# CAN_ADM3053.net
KiCad netlist of a schematic drawn in Altium Designer
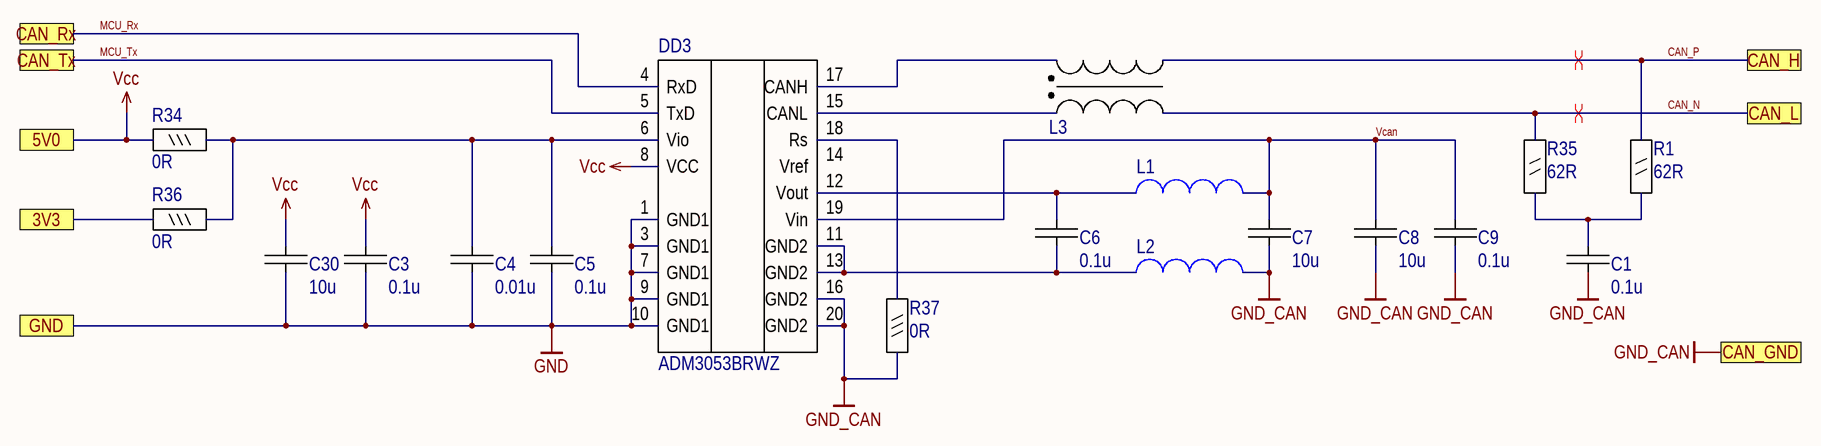
[diagram p0: CAN_ADM3053.SchDoc]

(export (version "E")
  (design (tool "Eeschema 10.0.6"))
  (components
    (comp (ref "C1")
      (value "0.1u")
      (footprint "C0603_IPC")
      (description "0.1uF ±10% 50V Ceramic Capacitor X7R 0603 (1608 Metric)")
      (fields (field (name "PARTNUMBER") "0.1u 50V") (field (name "MPN") "CL10B104KB8NNND"))
      (libsource (lib "DB_res_cap_ind") (part "C0603_GOST"))
    )
    (comp (ref "C3")
      (value "0.1u")
      (footprint "C0603_IPC")
      (description "0.1uF ±10% 50V Ceramic Capacitor X7R 0603 (1608 Metric)")
      (fields (field (name "PARTNUMBER") "0.1u 50V") (field (name "MPN") "CL10B104KB8NNND"))
      (libsource (lib "DB_res_cap_ind") (part "C0603_GOST"))
    )
    (comp (ref "C4")
      (value "0.01u")
      (footprint "C0603_IPC")
      (description "0.01uF ±10% 50V Ceramic Capacitor X7R 0603 (1608 Metric)")
      (fields (field (name "PARTNUMBER") "0.01u 50V") (field (name "MPN") "CC0603KRX7R9BB103"))
      (libsource (lib "DB_res_cap_ind") (part "C0603_GOST"))
    )
    (comp (ref "C5")
      (value "0.1u")
      (footprint "C0603_IPC")
      (description "0.1uF ±10% 50V Ceramic Capacitor X7R 0603 (1608 Metric)")
      (fields (field (name "PARTNUMBER") "0.1u 50V") (field (name "MPN") "CL10B104KB8NNND"))
      (libsource (lib "DB_res_cap_ind") (part "C0603_GOST"))
    )
    (comp (ref "C6")
      (value "0.1u")
      (footprint "C0603_IPC")
      (description "0.1uF ±10% 50V Ceramic Capacitor X7R 0603 (1608 Metric)")
      (fields (field (name "PARTNUMBER") "0.1u 50V") (field (name "MPN") "CL10B104KB8NNND"))
      (libsource (lib "DB_res_cap_ind") (part "C0603_GOST"))
    )
    (comp (ref "C7")
      (value "10u")
      (footprint "C0805_IPC")
      (description "10µF ±10% 10V Ceramic Capacitor X7R 0805 (2012 Metric)")
      (fields (field (name "PARTNUMBER") "10u 10V") (field (name "MPN") "CL21B106KPQNNNE"))
      (libsource (lib "DB_res_cap_ind") (part "C0603_GOST"))
    )
    (comp (ref "C8")
      (value "10u")
      (footprint "C0805_IPC")
      (description "10µF ±10% 10V Ceramic Capacitor X7R 0805 (2012 Metric)")
      (fields (field (name "PARTNUMBER") "10u 10V") (field (name "MPN") "CL21B106KPQNNNE"))
      (libsource (lib "DB_res_cap_ind") (part "C0603_GOST"))
    )
    (comp (ref "C9")
      (value "0.1u")
      (footprint "C0603_IPC")
      (description "0.1uF ±10% 50V Ceramic Capacitor X7R 0603 (1608 Metric)")
      (fields (field (name "PARTNUMBER") "0.1u 50V") (field (name "MPN") "CL10B104KB8NNND"))
      (libsource (lib "DB_res_cap_ind") (part "C0603_GOST"))
    )
    (comp (ref "C30")
      (value "10u")
      (footprint "C0805_IPC")
      (description "10µF ±10% 10V Ceramic Capacitor X7R 0805 (2012 Metric)")
      (fields (field (name "PARTNUMBER") "10u 10V") (field (name "MPN") "CL21B106KPQNNNE"))
      (libsource (lib "DB_res_cap_ind") (part "C0603_GOST"))
    )
    (comp (ref "DD3")
      (value "ADM3053BRWZ")
      (footprint "SOIC20W")
      (description "DGTL ISO 2.5KV 2CH CAN 20SOIC")
      (libsource (lib "DB_IC") (part "ADM3053"))
    )
    (comp (ref "L1")
      (value "BLM18AG102SN1D")
      (footprint "ind0603")
      (description "1 kOhms @ 100MHz 1 Ferrite Bead 0603 (1608 Metric) 400mA 500 mOhm")
      (fields (field (name "PARTNUMBER") "BLM18AG102") (field (name "TOLERANCE") "±25%"))
      (libsource (lib "DB_res_cap_ind") (part "INDUCTOR"))
    )
    (comp (ref "L2")
      (value "BLM18AG102SN1D")
      (footprint "ind0603")
      (description "1 kOhms @ 100MHz 1 Ferrite Bead 0603 (1608 Metric) 400mA 500 mOhm")
      (fields (field (name "PARTNUMBER") "BLM18AG102") (field (name "TOLERANCE") "±25%"))
      (libsource (lib "DB_res_cap_ind") (part "INDUCTOR"))
    )
    (comp (ref "L3")
      (value "DLW21SN900SQ2L")
      (footprint "DLW21S 0805")
      (description "2 Line Common Mode Choke Surface Mount 90 Ohms @ 100MHz 330mA DCR 350 mOhm")
      (fields (field (name "MANUFACTURER") "Murata"))
      (libsource (lib "DB_res_cap_ind") (part "DLW21SN_SQ"))
    )
    (comp (ref "R1")
      (value "62R")
      (footprint "R0805")
      (description "62 Ohms ±5% 0.125W, 1/8W Chip Resistor 0805 (2012 Metric) Moisture Resistant Thick Film")
      (fields (field (name "MPN") "RC0805JR-0762RL") (field (name "TOLERANCE") "0,05"))
      (libsource (lib "DB_res_cap_ind") (part "R0805"))
    )
    (comp (ref "R34")
      (value "0R")
      (footprint "R0603")
      (description "0 Ohms Jumper 0.1W, 1/10W Chip Resistor 0603 (1608 Metric) Moisture Resistant Thick Film")
      (fields (field (name "MPN") "RC0603FR-070RL") (field (name "TOLERANCE") "Jumper"))
      (libsource (lib "DB_res_cap_ind") (part "R0603"))
    )
    (comp (ref "R35")
      (value "62R")
      (footprint "R0805")
      (description "62 Ohms ±5% 0.125W, 1/8W Chip Resistor 0805 (2012 Metric) Moisture Resistant Thick Film")
      (fields (field (name "MPN") "RC0805JR-0762RL") (field (name "TOLERANCE") "0,05"))
      (libsource (lib "DB_res_cap_ind") (part "R0805"))
    )
    (comp (ref "R36")
      (value "0R")
      (footprint "R0603")
      (description "0 Ohms Jumper 0.1W, 1/10W Chip Resistor 0603 (1608 Metric) Moisture Resistant Thick Film")
      (fields (field (name "MPN") "RC0603FR-070RL") (field (name "TOLERANCE") "Jumper"))
      (libsource (lib "DB_res_cap_ind") (part "R0603"))
    )
    (comp (ref "R37")
      (value "0R")
      (footprint "R0603")
      (description "0 Ohms Jumper 0.1W, 1/10W Chip Resistor 0603 (1608 Metric) Moisture Resistant Thick Film")
      (fields (field (name "MPN") "RC0603FR-070RL") (field (name "TOLERANCE") "Jumper"))
      (libsource (lib "DB_res_cap_ind") (part "R0603"))
    )
  )
  (nets
    (net (code "1") (name "/3V3") (class "Default")
      (node (ref "R36") (pin "2") (pinfunction "2_2") (pintype "passive"))
    )
    (net (code "2") (name "/CAN_N") (class "Default")
      (node (ref "L3") (pin "3") (pinfunction "3_3") (pintype "passive"))
      (node (ref "R35") (pin "2") (pinfunction "2_2") (pintype "passive"))
    )
    (net (code "3") (name "/CAN_P") (class "Default")
      (node (ref "L3") (pin "2") (pinfunction "2_2") (pintype "passive"))
      (node (ref "R1") (pin "2") (pinfunction "2_2") (pintype "passive"))
    )
    (net (code "4") (name "/MCU_Rx") (class "Default")
      (node (ref "DD3") (pin "4") (pinfunction "RxD_4") (pintype "passive"))
    )
    (net (code "5") (name "/MCU_Tx") (class "Default")
      (node (ref "DD3") (pin "5") (pinfunction "TxD_5") (pintype "passive"))
    )
    (net (code "6") (name "/Vcan") (class "Default")
      (node (ref "C7") (pin "1") (pinfunction "1_1") (pintype "passive"))
      (node (ref "C8") (pin "1") (pinfunction "1_1") (pintype "passive"))
      (node (ref "C9") (pin "1") (pinfunction "1_1") (pintype "passive"))
      (node (ref "DD3") (pin "19") (pinfunction "Vin_19") (pintype "passive"))
      (node (ref "L1") (pin "2") (pinfunction "2_2") (pintype "passive"))
    )
    (net (code "7") (name "GND") (class "Default")
      (node (ref "C3") (pin "2") (pinfunction "2_2") (pintype "passive"))
      (node (ref "C30") (pin "2") (pinfunction "2_2") (pintype "passive"))
      (node (ref "C4") (pin "2") (pinfunction "2_2") (pintype "passive"))
      (node (ref "C5") (pin "2") (pinfunction "2_2") (pintype "passive"))
      (node (ref "DD3") (pin "1") (pinfunction "GND1_1") (pintype "passive"))
      (node (ref "DD3") (pin "10") (pinfunction "GND1_10") (pintype "passive"))
      (node (ref "DD3") (pin "3") (pinfunction "GND1_3") (pintype "passive"))
      (node (ref "DD3") (pin "7") (pinfunction "GND1_7") (pintype "passive"))
      (node (ref "DD3") (pin "9") (pinfunction "GND1_9") (pintype "passive"))
    )
    (net (code "8") (name "GND_CAN") (class "Default")
      (node (ref "C1") (pin "2") (pinfunction "2_2") (pintype "passive"))
      (node (ref "C7") (pin "2") (pinfunction "2_2") (pintype "passive"))
      (node (ref "C8") (pin "2") (pinfunction "2_2") (pintype "passive"))
      (node (ref "C9") (pin "2") (pinfunction "2_2") (pintype "passive"))
      (node (ref "DD3") (pin "16") (pinfunction "GND2_16") (pintype "passive"))
      (node (ref "DD3") (pin "20") (pinfunction "GND2_20") (pintype "passive"))
      (node (ref "L2") (pin "2") (pinfunction "2_2") (pintype "passive"))
      (node (ref "R37") (pin "1") (pinfunction "1_1") (pintype "passive"))
    )
    (net (code "9") (name "Net-(C1-Pad1)") (class "Default")
      (node (ref "C1") (pin "1") (pinfunction "1_1") (pintype "passive"))
      (node (ref "R1") (pin "1") (pinfunction "1_1") (pintype "passive"))
      (node (ref "R35") (pin "1") (pinfunction "1_1") (pintype "passive"))
    )
    (net (code "10") (name "Net-(C6-Pad2)") (class "Default")
      (node (ref "C6") (pin "2") (pinfunction "2_2") (pintype "passive"))
      (node (ref "DD3") (pin "11") (pinfunction "GND2_11") (pintype "passive"))
      (node (ref "DD3") (pin "13") (pinfunction "GND2_13") (pintype "passive"))
      (node (ref "L2") (pin "1") (pinfunction "1_1") (pintype "passive"))
    )
    (net (code "11") (name "Net-(DD3-CANH)") (class "Default")
      (node (ref "DD3") (pin "17") (pinfunction "CANH_17") (pintype "passive"))
      (node (ref "L3") (pin "1") (pinfunction "1_1") (pintype "passive"))
    )
    (net (code "12") (name "Net-(DD3-CANL)") (class "Default")
      (node (ref "DD3") (pin "15") (pinfunction "CANL_15") (pintype "passive"))
      (node (ref "L3") (pin "4") (pinfunction "4_4") (pintype "passive"))
    )
    (net (code "13") (name "Net-(DD3-Rs)") (class "Default")
      (node (ref "DD3") (pin "18") (pinfunction "Rs_18") (pintype "passive"))
      (node (ref "R37") (pin "2") (pinfunction "2_2") (pintype "passive"))
    )
    (net (code "14") (name "Net-(DD3-Vio)") (class "Default")
      (node (ref "C4") (pin "1") (pinfunction "1_1") (pintype "passive"))
      (node (ref "C5") (pin "1") (pinfunction "1_1") (pintype "passive"))
      (node (ref "DD3") (pin "6") (pinfunction "Vio_6") (pintype "passive"))
      (node (ref "R34") (pin "1") (pinfunction "1_1") (pintype "passive"))
      (node (ref "R36") (pin "1") (pinfunction "1_1") (pintype "passive"))
    )
    (net (code "15") (name "Net-(DD3-Vout)") (class "Default")
      (node (ref "C6") (pin "1") (pinfunction "1_1") (pintype "passive"))
      (node (ref "DD3") (pin "12") (pinfunction "Vout_12") (pintype "passive"))
      (node (ref "L1") (pin "1") (pinfunction "1_1") (pintype "passive"))
    )
    (net (code "16") (name "Vcc") (class "Default")
      (node (ref "C3") (pin "1") (pinfunction "1_1") (pintype "passive"))
      (node (ref "C30") (pin "1") (pinfunction "1_1") (pintype "passive"))
      (node (ref "DD3") (pin "8") (pinfunction "VCC_8") (pintype "passive"))
      (node (ref "R34") (pin "2") (pinfunction "2_2") (pintype "passive"))
    )
    (net (code "17") (name "unconnected-(DD3-NC-Pad2)") (class "Default")
      (node (ref "DD3") (pin "2") (pinfunction "NC_2") (pintype "tri_state"))
    )
    (net (code "18") (name "unconnected-(DD3-Vref-Pad14)") (class "Default")
      (node (ref "DD3") (pin "14") (pinfunction "Vref_14") (pintype "passive"))
    )
  )
)
